# LIXIE_II_Main.net
KiCad netlist of a schematic drawn in EAGLE
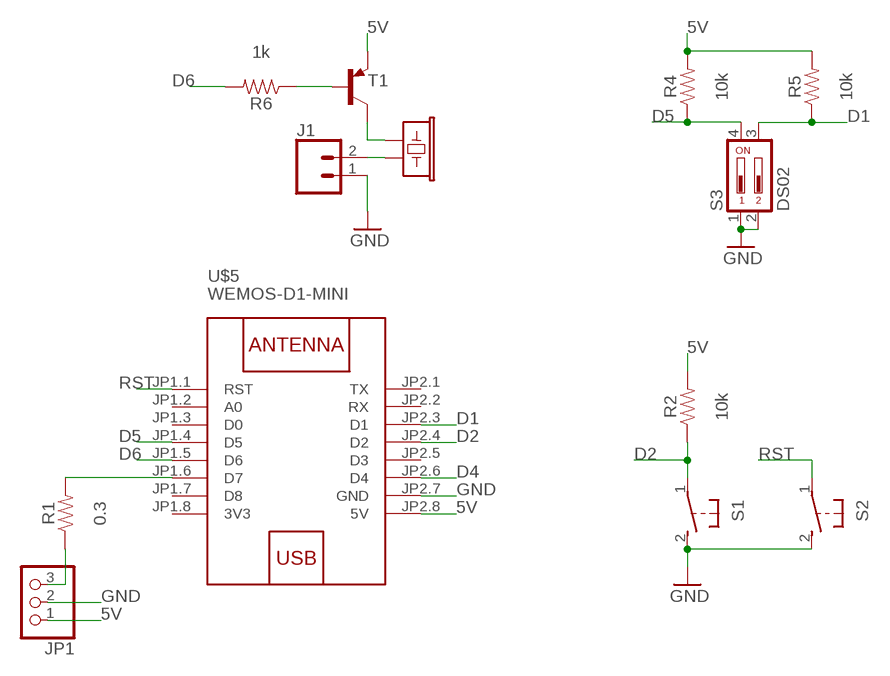
[diagram p0: schematic, sheet 1]

(export (version "E")
  (design (tool "Eeschema 10.0.6"))
  (components
    (comp (ref "J1")
      (value "CONN_02")
      (footprint "eagle-import:1X02")
      (libsource (lib "eagle-import") (part "CONN_02"))
    )
    (comp (ref "JP1")
      (value "PINHD-1X3")
      (footprint "eagle-import:1X03")
      (libsource (lib "eagle-import") (part "PINHD-1X3"))
    )
    (comp (ref "LS2")
      (value "BUZZER-PTH")
      (footprint "eagle-import:BUZZER-12MM")
      (libsource (lib "eagle-import") (part "BUZZER-PTH"))
    )
    (comp (ref "R1")
      (value "0.3")
      (footprint "eagle-import:0805")
      (libsource (lib "eagle-import") (part "0.3OHM-0805-1/8W-1%"))
    )
    (comp (ref "R2")
      (value "10k")
      (footprint "eagle-import:0805")
      (libsource (lib "eagle-import") (part "0.3OHM-0805-1/8W-1%"))
    )
    (comp (ref "R4")
      (value "10k")
      (footprint "eagle-import:0805")
      (libsource (lib "eagle-import") (part "0.3OHM-0805-1/8W-1%"))
    )
    (comp (ref "R5")
      (value "10k")
      (footprint "eagle-import:0805")
      (libsource (lib "eagle-import") (part "0.3OHM-0805-1/8W-1%"))
    )
    (comp (ref "R6")
      (value "1k")
      (footprint "eagle-import:0805")
      (libsource (lib "eagle-import") (part "0.3OHM-0805-1/8W-1%"))
    )
    (comp (ref "S1")
      (value "31-XX")
      (footprint "eagle-import:B3F-31XX")
      (libsource (lib "eagle-import") (part "31-XX"))
    )
    (comp (ref "S2")
      (value "31-XX")
      (footprint "eagle-import:B3F-31XX")
      (libsource (lib "eagle-import") (part "31-XX"))
    )
    (comp (ref "S3")
      (value "DS02")
      (footprint "eagle-import:DS-02")
      (fields (field (name "MPN") "MCNDS02"))
      (libsource (lib "eagle-import") (part "DS02"))
    )
    (comp (ref "T1")
      (value "-PNP-SOT23-EBC")
      (footprint "eagle-import:SOT23-EBC")
      (libsource (lib "eagle-import") (part "-PNP-SOT23-EBC"))
    )
    (comp (ref "U$5")
      (value "WEMOS-D1-MINI")
      (footprint "eagle-import:WEMOS-D1-MINI")
      (libsource (lib "eagle-import") (part "WEMOS-D1-MINI"))
    )
  )
  (nets
    (net (code "1") (name "/3V3") (class "Default")
      (node (ref "U$5") (pin "JP1.8") (pinfunction "3V3_JP1.8") (pintype "power_in"))
    )
    (net (code "2") (name "/5V") (class "Default")
      (node (ref "JP1") (pin "1") (pinfunction "1_1") (pintype "passive"))
      (node (ref "R2") (pin "2") (pinfunction "2_2") (pintype "passive"))
      (node (ref "R4") (pin "2") (pinfunction "2_2") (pintype "passive"))
      (node (ref "R5") (pin "2") (pinfunction "2_2") (pintype "passive"))
      (node (ref "T1") (pin "E") (pinfunction "E_E") (pintype "passive"))
      (node (ref "U$5") (pin "JP2.8") (pinfunction "5V_JP2.8") (pintype "power_in"))
    )
    (net (code "3") (name "/D1") (class "Default")
      (node (ref "R5") (pin "1") (pinfunction "1_1") (pintype "passive"))
      (node (ref "S3") (pin "3") (pinfunction "3_3") (pintype "passive"))
      (node (ref "U$5") (pin "JP2.3") (pinfunction "D1_JP2.3") (pintype "bidirectional"))
    )
    (net (code "4") (name "/D2") (class "Default")
      (node (ref "R2") (pin "1") (pinfunction "1_1") (pintype "passive"))
      (node (ref "S1") (pin "1") (pinfunction "P_1") (pintype "passive"))
      (node (ref "U$5") (pin "JP2.4") (pinfunction "D2_JP2.4") (pintype "bidirectional"))
    )
    (net (code "5") (name "/D4") (class "Default")
      (node (ref "U$5") (pin "JP2.6") (pinfunction "D4_JP2.6") (pintype "bidirectional"))
    )
    (net (code "6") (name "/D5") (class "Default")
      (node (ref "R4") (pin "1") (pinfunction "1_1") (pintype "passive"))
      (node (ref "S3") (pin "4") (pinfunction "4_4") (pintype "passive"))
      (node (ref "U$5") (pin "JP1.4") (pinfunction "D5_JP1.4") (pintype "bidirectional"))
    )
    (net (code "7") (name "/D6") (class "Default")
      (node (ref "R6") (pin "2") (pinfunction "2_2") (pintype "passive"))
      (node (ref "U$5") (pin "JP1.5") (pinfunction "D6_JP1.5") (pintype "bidirectional"))
    )
    (net (code "8") (name "/RST") (class "Default")
      (node (ref "S2") (pin "1") (pinfunction "P_1") (pintype "passive"))
      (node (ref "U$5") (pin "JP1.1") (pinfunction "RST_JP1.1") (pintype "bidirectional"))
    )
    (net (code "9") (name "GND") (class "Default")
      (node (ref "J1") (pin "1") (pinfunction "1_1") (pintype "passive"))
      (node (ref "JP1") (pin "2") (pinfunction "2_2") (pintype "passive"))
      (node (ref "S1") (pin "2") (pinfunction "S_2") (pintype "passive"))
      (node (ref "S2") (pin "2") (pinfunction "S_2") (pintype "passive"))
      (node (ref "S3") (pin "1") (pinfunction "1_1") (pintype "passive"))
      (node (ref "S3") (pin "2") (pinfunction "2_2") (pintype "passive"))
      (node (ref "U$5") (pin "JP2.7") (pinfunction "GND_JP2.7") (pintype "power_in"))
    )
    (net (code "10") (name "Net-(JP1-Pad3)") (class "Default")
      (node (ref "JP1") (pin "3") (pinfunction "3_3") (pintype "passive"))
      (node (ref "R1") (pin "1") (pinfunction "1_1") (pintype "passive"))
    )
    (net (code "11") (name "Net-(LS2-1)") (class "Default")
      (node (ref "LS2") (pin "+") (pinfunction "1_+") (pintype "passive"))
      (node (ref "T1") (pin "C") (pinfunction "C_C") (pintype "passive"))
    )
    (net (code "12") (name "Net-(LS2-2)") (class "Default")
      (node (ref "J1") (pin "2") (pinfunction "2_2") (pintype "passive"))
      (node (ref "LS2") (pin "-") (pinfunction "2_-") (pintype "passive"))
    )
    (net (code "13") (name "Net-(R6-Pad1)") (class "Default")
      (node (ref "R6") (pin "1") (pinfunction "1_1") (pintype "passive"))
      (node (ref "T1") (pin "B") (pinfunction "B_B") (pintype "passive"))
    )
    (net (code "14") (name "Net-(U$5-D7)") (class "Default")
      (node (ref "R1") (pin "2") (pinfunction "2_2") (pintype "passive"))
      (node (ref "U$5") (pin "JP1.6") (pinfunction "D7_JP1.6") (pintype "bidirectional"))
    )
    (net (code "15") (name "unconnected-(U$5-A0-PadJP1.2)") (class "Default")
      (node (ref "U$5") (pin "JP1.2") (pinfunction "A0_JP1.2") (pintype "bidirectional"))
    )
    (net (code "16") (name "unconnected-(U$5-D0-PadJP1.3)") (class "Default")
      (node (ref "U$5") (pin "JP1.3") (pinfunction "D0_JP1.3") (pintype "bidirectional"))
    )
    (net (code "17") (name "unconnected-(U$5-D3-PadJP2.5)") (class "Default")
      (node (ref "U$5") (pin "JP2.5") (pinfunction "D3_JP2.5") (pintype "bidirectional"))
    )
    (net (code "18") (name "unconnected-(U$5-D8-PadJP1.7)") (class "Default")
      (node (ref "U$5") (pin "JP1.7") (pinfunction "D8_JP1.7") (pintype "bidirectional"))
    )
    (net (code "19") (name "unconnected-(U$5-RX-PadJP2.2)") (class "Default")
      (node (ref "U$5") (pin "JP2.2") (pinfunction "RX_JP2.2") (pintype "bidirectional"))
    )
    (net (code "20") (name "unconnected-(U$5-TX-PadJP2.1)") (class "Default")
      (node (ref "U$5") (pin "JP2.1") (pinfunction "TX_JP2.1") (pintype "bidirectional"))
    )
  )
)
